# Power.net
KiCad netlist of a schematic drawn in Altium Designer
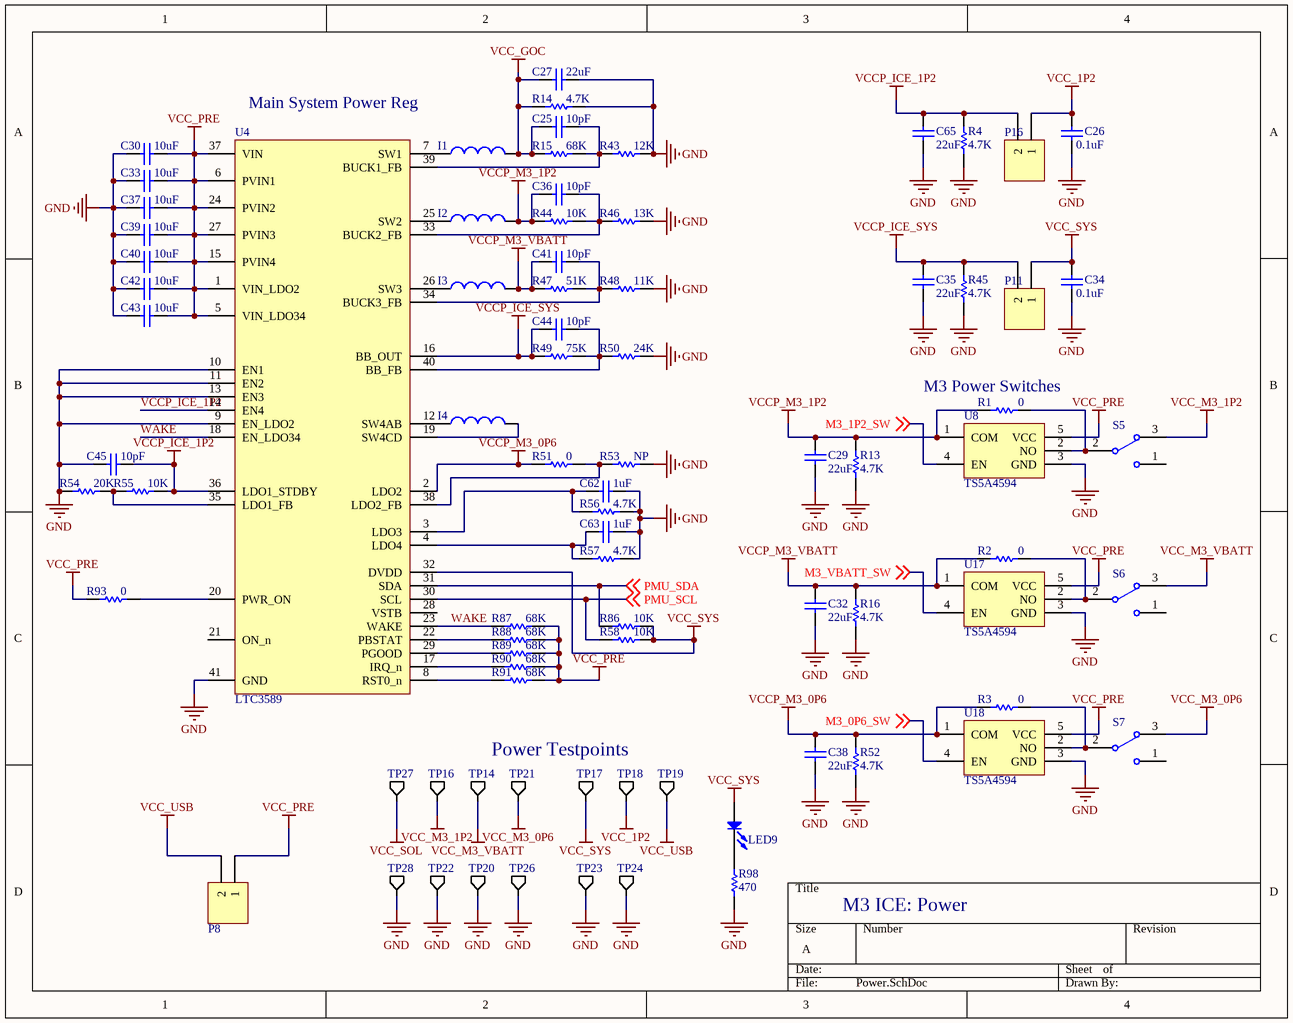
[diagram p0: Power.SchDoc]

(export (version "E")
  (design (tool "Eeschema 10.0.6"))
  (components
    (comp (ref "C25")
      (value "10pF")
      (footprint "0402")
      (description "Capacitor (Semiconductor SIM Model)")
      (fields
        (field (name "DISTPARTNO") "445-1235-1-ND")
        (field (name "MANPARTNO") "C1005C0G1H100D")
        (field (name "PUBLISHER") "Altium Limited")
      )
      (libsource (lib "Miscellaneous Devices") (part "Cap Semi"))
    )
    (comp (ref "C26")
      (value "0.1uF")
      (footprint "1608[0603]")
      (description "Capacitor (Semiconductor SIM Model)")
      (fields
        (field (name "DISTPARTNO") "1276-1005-1-ND")
        (field (name "MANPARTNO") "CL10B104KO8NNNC")
        (field (name "PUBLISHER") "Altium Limited")
      )
      (libsource (lib "Miscellaneous Devices") (part "Cap Semi"))
    )
    (comp (ref "C27")
      (value "22uF")
      (footprint "0805")
      (description "Capacitor (Semiconductor SIM Model)")
      (fields
        (field (name "DISTPARTNO") "587-2782-1-ND")
        (field (name "MANPARTNO") "LMK316AB7226ML-TR")
        (field (name "PUBLISHER") "Altium Limited")
      )
      (libsource (lib "M3") (part "Cap Chip"))
    )
    (comp (ref "C29")
      (value "22uF")
      (footprint "0805")
      (description "Capacitor (Semiconductor SIM Model)")
      (fields
        (field (name "DISTPARTNO") "587-2782-1-ND")
        (field (name "MANPARTNO") "LMK316AB7226ML-TR")
        (field (name "PUBLISHER") "Altium Limited")
      )
      (libsource (lib "M3") (part "Cap Chip"))
    )
    (comp (ref "C30")
      (value "10uF")
      (footprint "0805")
      (description "Capacitor (Semiconductor SIM Model)")
      (fields
        (field (name "DISTPARTNO") "445-6857-1-ND")
        (field (name "MANPARTNO") "C2012X7R1A106K")
        (field (name "PUBLISHER") "Altium Limited")
      )
      (libsource (lib "M3") (part "Cap Chip"))
    )
    (comp (ref "C32")
      (value "22uF")
      (footprint "0805")
      (description "Capacitor (Semiconductor SIM Model)")
      (fields
        (field (name "DISTPARTNO") "587-2782-1-ND")
        (field (name "MANPARTNO") "LMK316AB7226ML-TR")
        (field (name "PUBLISHER") "Altium Limited")
      )
      (libsource (lib "M3") (part "Cap Chip"))
    )
    (comp (ref "C33")
      (value "10uF")
      (footprint "0805")
      (description "Capacitor (Semiconductor SIM Model)")
      (fields
        (field (name "DISTPARTNO") "445-6857-1-ND")
        (field (name "MANPARTNO") "C2012X7R1A106K")
        (field (name "PUBLISHER") "Altium Limited")
      )
      (libsource (lib "M3") (part "Cap Chip"))
    )
    (comp (ref "C34")
      (value "0.1uF")
      (footprint "1608[0603]")
      (description "Capacitor (Semiconductor SIM Model)")
      (fields
        (field (name "DISTPARTNO") "1276-1005-1-ND")
        (field (name "MANPARTNO") "CL10B104KO8NNNC")
        (field (name "PUBLISHER") "Altium Limited")
      )
      (libsource (lib "Miscellaneous Devices") (part "Cap Semi"))
    )
    (comp (ref "C35")
      (value "22uF")
      (footprint "0805")
      (description "Capacitor (Semiconductor SIM Model)")
      (fields
        (field (name "DISTPARTNO") "587-2782-1-ND")
        (field (name "MANPARTNO") "LMK316AB7226ML-TR")
        (field (name "PUBLISHER") "Altium Limited")
      )
      (libsource (lib "M3") (part "Cap Chip"))
    )
    (comp (ref "C36")
      (value "10pF")
      (footprint "0402")
      (description "Capacitor (Semiconductor SIM Model)")
      (fields
        (field (name "DISTPARTNO") "445-1235-1-ND")
        (field (name "MANPARTNO") "C1005C0G1H100D")
        (field (name "PUBLISHER") "Altium Limited")
      )
      (libsource (lib "Miscellaneous Devices") (part "Cap Semi"))
    )
    (comp (ref "C37")
      (value "10uF")
      (footprint "0805")
      (description "Capacitor (Semiconductor SIM Model)")
      (fields
        (field (name "DISTPARTNO") "445-6857-1-ND")
        (field (name "MANPARTNO") "C2012X7R1A106K")
        (field (name "PUBLISHER") "Altium Limited")
      )
      (libsource (lib "M3") (part "Cap Chip"))
    )
    (comp (ref "C38")
      (value "22uF")
      (footprint "0805")
      (description "Capacitor (Semiconductor SIM Model)")
      (fields
        (field (name "DISTPARTNO") "587-2782-1-ND")
        (field (name "MANPARTNO") "LMK316AB7226ML-TR")
        (field (name "PUBLISHER") "Altium Limited")
      )
      (libsource (lib "M3") (part "Cap Chip"))
    )
    (comp (ref "C39")
      (value "10uF")
      (footprint "0805")
      (description "Capacitor (Semiconductor SIM Model)")
      (fields
        (field (name "DISTPARTNO") "445-6857-1-ND")
        (field (name "MANPARTNO") "C2012X7R1A106K")
        (field (name "PUBLISHER") "Altium Limited")
      )
      (libsource (lib "M3") (part "Cap Chip"))
    )
    (comp (ref "C40")
      (value "10uF")
      (footprint "0805")
      (description "Capacitor (Semiconductor SIM Model)")
      (fields
        (field (name "DISTPARTNO") "445-6857-1-ND")
        (field (name "MANPARTNO") "C2012X7R1A106K")
        (field (name "PUBLISHER") "Altium Limited")
      )
      (libsource (lib "M3") (part "Cap Chip"))
    )
    (comp (ref "C41")
      (value "10pF")
      (footprint "0402")
      (description "Capacitor (Semiconductor SIM Model)")
      (fields
        (field (name "DISTPARTNO") "445-1235-1-ND")
        (field (name "MANPARTNO") "C1005C0G1H100D")
        (field (name "PUBLISHER") "Altium Limited")
      )
      (libsource (lib "Miscellaneous Devices") (part "Cap Semi"))
    )
    (comp (ref "C42")
      (value "10uF")
      (footprint "0805")
      (description "Capacitor (Semiconductor SIM Model)")
      (fields
        (field (name "DISTPARTNO") "445-6857-1-ND")
        (field (name "MANPARTNO") "C2012X7R1A106K")
        (field (name "PUBLISHER") "Altium Limited")
      )
      (libsource (lib "M3") (part "Cap Chip"))
    )
    (comp (ref "C43")
      (value "10uF")
      (footprint "0805")
      (description "Capacitor (Semiconductor SIM Model)")
      (fields
        (field (name "DISTPARTNO") "445-6857-1-ND")
        (field (name "MANPARTNO") "C2012X7R1A106K")
        (field (name "PUBLISHER") "Altium Limited")
      )
      (libsource (lib "M3") (part "Cap Chip"))
    )
    (comp (ref "C44")
      (value "10pF")
      (footprint "0402")
      (description "Capacitor (Semiconductor SIM Model)")
      (fields
        (field (name "DISTPARTNO") "445-1235-1-ND")
        (field (name "MANPARTNO") "C1005C0G1H100D")
        (field (name "PUBLISHER") "Altium Limited")
      )
      (libsource (lib "Miscellaneous Devices") (part "Cap Semi"))
    )
    (comp (ref "C45")
      (value "10pF")
      (footprint "0402")
      (description "Capacitor (Semiconductor SIM Model)")
      (fields
        (field (name "DISTPARTNO") "445-1235-1-ND")
        (field (name "MANPARTNO") "C1005C0G1H100D")
        (field (name "PUBLISHER") "Altium Limited")
      )
      (libsource (lib "Miscellaneous Devices") (part "Cap Semi"))
    )
    (comp (ref "C62")
      (value "1uF")
      (footprint "0402")
      (description "Capacitor (Semiconductor SIM Model)")
      (fields
        (field (name "DISTPARTNO") "445-4991-1-ND")
        (field (name "MANPARTNO") "C1005X5R1A105M")
        (field (name "PUBLISHER") "Altium Limited")
      )
      (libsource (lib "Miscellaneous Devices") (part "Cap Semi"))
    )
    (comp (ref "C63")
      (value "1uF")
      (footprint "0402")
      (description "Capacitor (Semiconductor SIM Model)")
      (fields
        (field (name "DISTPARTNO") "445-4991-1-ND")
        (field (name "MANPARTNO") "C1005X5R1A105M")
        (field (name "PUBLISHER") "Altium Limited")
      )
      (libsource (lib "Miscellaneous Devices") (part "Cap Semi"))
    )
    (comp (ref "C65")
      (value "22uF")
      (footprint "0805")
      (description "Capacitor (Semiconductor SIM Model)")
      (fields
        (field (name "DISTPARTNO") "587-2782-1-ND")
        (field (name "MANPARTNO") "LMK316AB7226ML-TR")
        (field (name "PUBLISHER") "Altium Limited")
      )
      (libsource (lib "M3") (part "Cap Chip"))
    )
    (comp (ref "I1")
      (value "NR5040T1R5N")
      (footprint "INDUCTOR_.118x.142mm")
      (fields (field (name "DISTPARTNO") "541-1327-1-ND") (field (name "MANPARTNO") "IHLP1212AEER1R0M11"))
      (libsource (lib "M3") (part "IHLP1212"))
    )
    (comp (ref "I2")
      (value "NR5040T1R5N")
      (footprint "INDUCTOR_.118x.142mm")
      (fields (field (name "DISTPARTNO") "541-1327-1-ND") (field (name "MANPARTNO") "IHLP1212AEER1R0M11"))
      (libsource (lib "M3") (part "IHLP1212"))
    )
    (comp (ref "I3")
      (value "NR5040T1R5N")
      (footprint "INDUCTOR_.118x.142mm")
      (fields (field (name "DISTPARTNO") "541-1327-1-ND") (field (name "MANPARTNO") "IHLP1212AEER1R0M11"))
      (libsource (lib "M3") (part "IHLP1212"))
    )
    (comp (ref "I4")
      (value "NR5040T1R5N")
      (footprint "INDUCTOR_.118x.142mm")
      (fields (field (name "DISTPARTNO") "541-1327-1-ND") (field (name "MANPARTNO") "IHLP1212AEER1R0M11"))
      (libsource (lib "M3") (part "IHLP1212"))
    )
    (comp (ref "LED9")
      (value "LED 1206")
      (footprint "1206_LED")
      (fields (field (name "DISTPARTNO") "160-1169-1-ND") (field (name "MANPARTNO") "LTST-C150GKT"))
      (libsource (lib "M3") (part "LED 1206"))
    )
    (comp (ref "P8")
      (value "Header 2")
      (footprint "HDR1X2")
      (description "Header, 2-Pin")
      (fields (field (name "PUBLISHER") "Altium Limited"))
      (libsource (lib "Miscellaneous Connectors") (part "Header 2"))
    )
    (comp (ref "P11")
      (value "Header 2")
      (footprint "HDR1X2")
      (description "Header, 2-Pin")
      (fields (field (name "PUBLISHER") "Altium Limited"))
      (libsource (lib "Miscellaneous Connectors") (part "Header 2"))
    )
    (comp (ref "P16")
      (value "Header 2")
      (footprint "HDR1X2")
      (description "Header, 2-Pin")
      (fields (field (name "PUBLISHER") "Altium Limited"))
      (libsource (lib "Miscellaneous Connectors") (part "Header 2"))
    )
    (comp (ref "R1")
      (value "0")
      (footprint "0603")
      (description "Semiconductor Resistor")
      (fields
        (field (name "DISTPARTNO") "P0.0GCT-ND")
        (field (name "MANPARTNO") "ERJ-3GEY0R00V")
        (field (name "PUBLISHER") "Altium Limited")
      )
      (libsource (lib "M3") (part "Res Chip"))
    )
    (comp (ref "R2")
      (value "0")
      (footprint "0603")
      (description "Semiconductor Resistor")
      (fields
        (field (name "DISTPARTNO") "P0.0GCT-ND")
        (field (name "MANPARTNO") "ERJ-3GEY0R00V")
        (field (name "PUBLISHER") "Altium Limited")
      )
      (libsource (lib "M3") (part "Res Chip"))
    )
    (comp (ref "R3")
      (value "0")
      (footprint "0603")
      (description "Semiconductor Resistor")
      (fields
        (field (name "DISTPARTNO") "P0.0GCT-ND")
        (field (name "MANPARTNO") "ERJ-3GEY0R00V")
        (field (name "PUBLISHER") "Altium Limited")
      )
      (libsource (lib "M3") (part "Res Chip"))
    )
    (comp (ref "R4")
      (value "4.7K")
      (footprint "0603")
      (description "Semiconductor Resistor")
      (fields
        (field (name "DISTPARTNO") "P4.7KGCT-ND")
        (field (name "MANPARTNO") "ERJ-3GEYJ472V")
        (field (name "PUBLISHER") "Altium Limited")
      )
      (libsource (lib "M3") (part "Res Chip"))
    )
    (comp (ref "R13")
      (value "4.7K")
      (footprint "0603")
      (description "Semiconductor Resistor")
      (fields
        (field (name "DISTPARTNO") "P4.7KGCT-ND")
        (field (name "MANPARTNO") "ERJ-3GEYJ472V")
        (field (name "PUBLISHER") "Altium Limited")
      )
      (libsource (lib "M3") (part "Res Chip"))
    )
    (comp (ref "R14")
      (value "4.7K")
      (footprint "0603")
      (description "Semiconductor Resistor")
      (fields
        (field (name "DISTPARTNO") "P4.7KGCT-ND")
        (field (name "MANPARTNO") "ERJ-3GEYJ472V")
        (field (name "PUBLISHER") "Altium Limited")
      )
      (libsource (lib "M3") (part "Res Chip"))
    )
    (comp (ref "R15")
      (value "68K")
      (footprint "0402")
      (description "Semiconductor Resistor")
      (fields
        (field (name "DISTPARTNO") "P68.0KLCT-ND")
        (field (name "MANPARTNO") "ERJ-2RKF6802X")
        (field (name "PUBLISHER") "Altium Limited")
      )
      (libsource (lib "M3") (part "Res Chip"))
    )
    (comp (ref "R16")
      (value "4.7K")
      (footprint "0603")
      (description "Semiconductor Resistor")
      (fields
        (field (name "DISTPARTNO") "P4.7KGCT-ND")
        (field (name "MANPARTNO") "ERJ-3GEYJ472V")
        (field (name "PUBLISHER") "Altium Limited")
      )
      (libsource (lib "M3") (part "Res Chip"))
    )
    (comp (ref "R43")
      (value "12K")
      (footprint "0402")
      (description "Semiconductor Resistor")
      (fields
        (field (name "DISTPARTNO") "P12.0KLCT-ND")
        (field (name "MANPARTNO") "ERJ-2RKF1202X")
        (field (name "PUBLISHER") "Altium Limited")
      )
      (libsource (lib "M3") (part "Res Chip"))
    )
    (comp (ref "R44")
      (value "10K")
      (footprint "0402")
      (description "Semiconductor Resistor")
      (fields
        (field (name "DISTPARTNO") "P10.0KLCT-ND")
        (field (name "MANPARTNO") "ERJ-2RKF1002X")
        (field (name "PUBLISHER") "Altium Limited")
      )
      (libsource (lib "M3") (part "Res Chip"))
    )
    (comp (ref "R45")
      (value "4.7K")
      (footprint "0603")
      (description "Semiconductor Resistor")
      (fields
        (field (name "DISTPARTNO") "P4.7KGCT-ND")
        (field (name "MANPARTNO") "ERJ-3GEYJ472V")
        (field (name "PUBLISHER") "Altium Limited")
      )
      (libsource (lib "M3") (part "Res Chip"))
    )
    (comp (ref "R46")
      (value "13K")
      (footprint "0402")
      (description "Semiconductor Resistor")
      (fields
        (field (name "DISTPARTNO") "311-13.0KLRCT-ND")
        (field (name "MANPARTNO") "RC0402FR-0713KL")
        (field (name "PUBLISHER") "Altium Limited")
      )
      (libsource (lib "M3") (part "Res Chip"))
    )
    (comp (ref "R47")
      (value "51K")
      (footprint "0402")
      (description "Semiconductor Resistor")
      (fields
        (field (name "DISTPARTNO") "P51.0KLCT-ND")
        (field (name "MANPARTNO") "ERJ-2RKF5102X")
        (field (name "PUBLISHER") "Altium Limited")
      )
      (libsource (lib "M3") (part "Res Chip"))
    )
    (comp (ref "R48")
      (value "11K")
      (footprint "0402")
      (description "Semiconductor Resistor")
      (fields
        (field (name "DISTPARTNO") "P11.0KLCT-ND")
        (field (name "MANPARTNO") "ERJ-2RKF1102X")
        (field (name "PUBLISHER") "Altium Limited")
      )
      (libsource (lib "M3") (part "Res Chip"))
    )
    (comp (ref "R49")
      (value "75K")
      (footprint "0402")
      (description "Semiconductor Resistor")
      (fields
        (field (name "DISTPARTNO") "P75.0KLCT-ND")
        (field (name "MANPARTNO") "ERJ-2RKF7502X")
        (field (name "PUBLISHER") "Altium Limited")
      )
      (libsource (lib "M3") (part "Res Chip"))
    )
    (comp (ref "R50")
      (value "24K")
      (footprint "0402")
      (description "Semiconductor Resistor")
      (fields
        (field (name "DISTPARTNO") "RMCF0402FT24K0CT-ND")
        (field (name "MANPARTNO") "RMCF0402FT24K0")
        (field (name "PUBLISHER") "Altium Limited")
      )
      (libsource (lib "M3") (part "Res Chip"))
    )
    (comp (ref "R51")
      (value "0")
      (footprint "0402")
      (description "Semiconductor Resistor")
      (fields
        (field (name "DISTPARTNO") "P0.0JCT-ND")
        (field (name "MANPARTNO") "ERJ-2GE0R00X")
        (field (name "PUBLISHER") "Altium Limited")
      )
      (libsource (lib "M3") (part "Res Chip"))
    )
    (comp (ref "R52")
      (value "4.7K")
      (footprint "0603")
      (description "Semiconductor Resistor")
      (fields
        (field (name "DISTPARTNO") "P4.7KGCT-ND")
        (field (name "MANPARTNO") "ERJ-3GEYJ472V")
        (field (name "PUBLISHER") "Altium Limited")
      )
      (libsource (lib "M3") (part "Res Chip"))
    )
    (comp (ref "R53")
      (value "NP")
      (footprint "0402")
      (description "Semiconductor Resistor")
      (fields (field (name "Comment") "Res Chip") (field (name "PUBLISHER") "Altium Limited"))
      (libsource (lib "M3") (part "Res Chip"))
    )
    (comp (ref "R54")
      (value "20K")
      (footprint "0402")
      (description "Semiconductor Resistor")
      (fields
        (field (name "DISTPARTNO") "P20.0KLCT-ND")
        (field (name "MANPARTNO") "ERJ-2RKF2002X")
        (field (name "PUBLISHER") "Altium Limited")
      )
      (libsource (lib "M3") (part "Res Chip"))
    )
    (comp (ref "R55")
      (value "10K")
      (footprint "0402")
      (description "Semiconductor Resistor")
      (fields
        (field (name "DISTPARTNO") "P10.0KLCT-ND")
        (field (name "MANPARTNO") "ERJ-2RKF1002X")
        (field (name "PUBLISHER") "Altium Limited")
      )
      (libsource (lib "M3") (part "Res Chip"))
    )
    (comp (ref "R56")
      (value "4.7K")
      (footprint "0402")
      (description "Semiconductor Resistor")
      (fields
        (field (name "DISTPARTNO") "P4.70KLCT-ND")
        (field (name "MANPARTNO") "ERJ-2RKF4701X")
        (field (name "PUBLISHER") "Altium Limited")
      )
      (libsource (lib "M3") (part "Res Chip"))
    )
    (comp (ref "R57")
      (value "4.7K")
      (footprint "0402")
      (description "Semiconductor Resistor")
      (fields
        (field (name "DISTPARTNO") "P4.70KLCT-ND")
        (field (name "MANPARTNO") "ERJ-2RKF4701X")
        (field (name "PUBLISHER") "Altium Limited")
      )
      (libsource (lib "M3") (part "Res Chip"))
    )
    (comp (ref "R58")
      (value "10K")
      (footprint "0402")
      (description "Semiconductor Resistor")
      (fields
        (field (name "DISTPARTNO") "P10.0KLCT-ND")
        (field (name "MANPARTNO") "ERJ-2RKF1002X")
        (field (name "PUBLISHER") "Altium Limited")
      )
      (libsource (lib "M3") (part "Res Chip"))
    )
    (comp (ref "R86")
      (value "10K")
      (footprint "0402")
      (description "Semiconductor Resistor")
      (fields
        (field (name "DISTPARTNO") "P10.0KLCT-ND")
        (field (name "MANPARTNO") "ERJ-2RKF1002X")
        (field (name "PUBLISHER") "Altium Limited")
      )
      (libsource (lib "M3") (part "Res Chip"))
    )
    (comp (ref "R87")
      (value "68K")
      (footprint "0402")
      (description "Semiconductor Resistor")
      (fields
        (field (name "DISTPARTNO") "P68.0KLCT-ND")
        (field (name "MANPARTNO") "ERJ-2RKF6802X")
        (field (name "PUBLISHER") "Altium Limited")
      )
      (libsource (lib "M3") (part "Res Chip"))
    )
    (comp (ref "R88")
      (value "68K")
      (footprint "0402")
      (description "Semiconductor Resistor")
      (fields
        (field (name "DISTPARTNO") "P68.0KLCT-ND")
        (field (name "MANPARTNO") "ERJ-2RKF6802X")
        (field (name "PUBLISHER") "Altium Limited")
      )
      (libsource (lib "M3") (part "Res Chip"))
    )
    (comp (ref "R89")
      (value "68K")
      (footprint "0402")
      (description "Semiconductor Resistor")
      (fields
        (field (name "DISTPARTNO") "P68.0KLCT-ND")
        (field (name "MANPARTNO") "ERJ-2RKF6802X")
        (field (name "PUBLISHER") "Altium Limited")
      )
      (libsource (lib "M3") (part "Res Chip"))
    )
    (comp (ref "R90")
      (value "68K")
      (footprint "0402")
      (description "Semiconductor Resistor")
      (fields
        (field (name "DISTPARTNO") "P68.0KLCT-ND")
        (field (name "MANPARTNO") "ERJ-2RKF6802X")
        (field (name "PUBLISHER") "Altium Limited")
      )
      (libsource (lib "M3") (part "Res Chip"))
    )
    (comp (ref "R91")
      (value "68K")
      (footprint "0402")
      (description "Semiconductor Resistor")
      (fields
        (field (name "DISTPARTNO") "P68.0KLCT-ND")
        (field (name "MANPARTNO") "ERJ-2RKF6802X")
        (field (name "PUBLISHER") "Altium Limited")
      )
      (libsource (lib "M3") (part "Res Chip"))
    )
    (comp (ref "R93")
      (value "0")
      (footprint "0402")
      (description "Semiconductor Resistor")
      (fields
        (field (name "DISTPARTNO") "P0.0JCT-ND")
        (field (name "MANPARTNO") "ERJ-2GE0R00X")
        (field (name "PUBLISHER") "Altium Limited")
      )
      (libsource (lib "M3") (part "Res Chip"))
    )
    (comp (ref "R98")
      (value "470")
      (footprint "0603")
      (description "Semiconductor Resistor")
      (fields
        (field (name "DISTPARTNO") "P470GCT-ND")
        (field (name "MANPARTNO") "ERJ-3GEYJ471V")
        (field (name "PUBLISHER") "Altium Limited")
      )
      (libsource (lib "M3") (part "Res Chip"))
    )
    (comp (ref "S5")
      (value "OS102011MS2QN1")
      (footprint "SPDT_SW2")
      (description "SPDT Slide Switch")
      (fields (field (name "DISTPARTNO") "CKN9565-ND"))
      (libsource (lib "M3") (part "OS102011MS2QN1"))
    )
    (comp (ref "S6")
      (value "OS102011MS2QN1")
      (footprint "SPDT_SW2")
      (description "SPDT Slide Switch")
      (fields (field (name "DISTPARTNO") "CKN9565-ND"))
      (libsource (lib "M3") (part "OS102011MS2QN1"))
    )
    (comp (ref "S7")
      (value "OS102011MS2QN1")
      (footprint "SPDT_SW2")
      (description "SPDT Slide Switch")
      (fields (field (name "DISTPARTNO") "CKN9565-ND"))
      (libsource (lib "M3") (part "OS102011MS2QN1"))
    )
    (comp (ref "TP14") (value "TP") (footprint "TP") (libsource (lib "M3") (part "TP")))
    (comp (ref "TP16") (value "TP") (footprint "TP") (libsource (lib "M3") (part "TP")))
    (comp (ref "TP17") (value "TP") (footprint "TP") (libsource (lib "M3") (part "TP")))
    (comp (ref "TP18") (value "TP") (footprint "TP") (libsource (lib "M3") (part "TP")))
    (comp (ref "TP19") (value "TP") (footprint "TP") (libsource (lib "M3") (part "TP")))
    (comp (ref "TP20") (value "TP") (footprint "TP") (libsource (lib "M3") (part "TP")))
    (comp (ref "TP21") (value "TP") (footprint "TP") (libsource (lib "M3") (part "TP")))
    (comp (ref "TP22") (value "TP") (footprint "TP") (libsource (lib "M3") (part "TP")))
    (comp (ref "TP23") (value "TP") (footprint "TP") (libsource (lib "M3") (part "TP")))
    (comp (ref "TP24") (value "TP") (footprint "TP") (libsource (lib "M3") (part "TP")))
    (comp (ref "TP26") (value "TP") (footprint "TP") (libsource (lib "M3") (part "TP")))
    (comp (ref "TP27") (value "TP") (footprint "TP") (libsource (lib "M3") (part "TP")))
    (comp (ref "TP28") (value "TP") (footprint "TP") (libsource (lib "M3") (part "TP")))
    (comp (ref "U4")
      (value "LTC3589")
      (footprint "QFN-40")
      (fields (field (name "DISTPARTNO") "LTC3589EUJ-2#PBF-ND") (field (name "MANPARTNO") "LTC3589EUJ-2#PBF"))
      (libsource (lib "M3") (part "LTC3589"))
    )
    (comp (ref "U8")
      (value "TS5A4594")
      (footprint "SOT25")
      (description "SPST Analog Switch")
      (fields (field (name "DISTPARTNO") "296-17705-1-ND") (field (name "MANPARTNO") "TS5A4594DBVR"))
      (libsource (lib "M3") (part "TS5A4594"))
    )
    (comp (ref "U17")
      (value "TS5A4594")
      (footprint "SOT25")
      (description "SPST Analog Switch")
      (fields (field (name "DISTPARTNO") "296-17705-1-ND") (field (name "MANPARTNO") "TS5A4594DBVR"))
      (libsource (lib "M3") (part "TS5A4594"))
    )
    (comp (ref "U18")
      (value "TS5A4594")
      (footprint "SOT25")
      (description "SPST Analog Switch")
      (fields (field (name "DISTPARTNO") "296-17705-1-ND") (field (name "MANPARTNO") "TS5A4594DBVR"))
      (libsource (lib "M3") (part "TS5A4594"))
    )
  )
  (nets
    (net (code "1") (name "/WAKE") (class "Default")
      (node (ref "R87") (pin "1") (pinfunction "1_1") (pintype "passive"))
      (node (ref "U4") (pin "18") (pinfunction "EN_LDO34_18") (pintype "passive"))
      (node (ref "U4") (pin "23") (pinfunction "WAKE_23") (pintype "passive"))
    )
    (net (code "2") (name "GND") (class "Default")
      (node (ref "C26") (pin "1") (pinfunction "1_1") (pintype "passive"))
      (node (ref "C27") (pin "1") (pinfunction "1_1") (pintype "passive"))
      (node (ref "C29") (pin "1") (pinfunction "1_1") (pintype "passive"))
      (node (ref "C30") (pin "2") (pinfunction "2_2") (pintype "passive"))
      (node (ref "C32") (pin "1") (pinfunction "1_1") (pintype "passive"))
      (node (ref "C33") (pin "2") (pinfunction "2_2") (pintype "passive"))
      (node (ref "C34") (pin "1") (pinfunction "1_1") (pintype "passive"))
      (node (ref "C35") (pin "1") (pinfunction "1_1") (pintype "passive"))
      (node (ref "C37") (pin "2") (pinfunction "2_2") (pintype "passive"))
      (node (ref "C38") (pin "1") (pinfunction "1_1") (pintype "passive"))
      (node (ref "C39") (pin "2") (pinfunction "2_2") (pintype "passive"))
      (node (ref "C40") (pin "2") (pinfunction "2_2") (pintype "passive"))
      (node (ref "C42") (pin "2") (pinfunction "2_2") (pintype "passive"))
      (node (ref "C43") (pin "2") (pinfunction "2_2") (pintype "passive"))
      (node (ref "C45") (pin "2") (pinfunction "2_2") (pintype "passive"))
      (node (ref "C62") (pin "1") (pinfunction "1_1") (pintype "passive"))
      (node (ref "C63") (pin "1") (pinfunction "1_1") (pintype "passive"))
      (node (ref "C65") (pin "2") (pinfunction "2_2") (pintype "passive"))
      (node (ref "R13") (pin "1") (pinfunction "1_1") (pintype "passive"))
      (node (ref "R14") (pin "1") (pinfunction "1_1") (pintype "passive"))
      (node (ref "R16") (pin "1") (pinfunction "1_1") (pintype "passive"))
      (node (ref "R4") (pin "2") (pinfunction "2_2") (pintype "passive"))
      (node (ref "R43") (pin "2") (pinfunction "2_2") (pintype "passive"))
      (node (ref "R45") (pin "1") (pinfunction "1_1") (pintype "passive"))
      (node (ref "R46") (pin "2") (pinfunction "2_2") (pintype "passive"))
      (node (ref "R48") (pin "2") (pinfunction "2_2") (pintype "passive"))
      (node (ref "R50") (pin "2") (pinfunction "2_2") (pintype "passive"))
      (node (ref "R52") (pin "1") (pinfunction "1_1") (pintype "passive"))
      (node (ref "R53") (pin "2") (pinfunction "2_2") (pintype "passive"))
      (node (ref "R54") (pin "1") (pinfunction "1_1") (pintype "passive"))
      (node (ref "R56") (pin "2") (pinfunction "2_2") (pintype "passive"))
      (node (ref "R57") (pin "2") (pinfunction "2_2") (pintype "passive"))
      (node (ref "R98") (pin "1") (pinfunction "1_1") (pintype "passive"))
      (node (ref "TP20") (pin "1") (pinfunction "A_1") (pintype "passive"))
      (node (ref "TP22") (pin "1") (pinfunction "A_1") (pintype "passive"))
      (node (ref "TP23") (pin "1") (pinfunction "A_1") (pintype "passive"))
      (node (ref "TP24") (pin "1") (pinfunction "A_1") (pintype "passive"))
      (node (ref "TP26") (pin "1") (pinfunction "A_1") (pintype "passive"))
      (node (ref "TP28") (pin "1") (pinfunction "A_1") (pintype "passive"))
      (node (ref "U17") (pin "3") (pinfunction "GND_3") (pintype "passive"))
      (node (ref "U18") (pin "3") (pinfunction "GND_3") (pintype "passive"))
      (node (ref "U4") (pin "10") (pinfunction "EN1_10") (pintype "passive"))
      (node (ref "U4") (pin "11") (pinfunction "EN2_11") (pintype "passive"))
      (node (ref "U4") (pin "13") (pinfunction "EN3_13") (pintype "passive"))
      (node (ref "U4") (pin "41") (pinfunction "GND_41") (pintype "passive"))
      (node (ref "U4") (pin "9") (pinfunction "EN_LDO2_9") (pintype "passive"))
      (node (ref "U8") (pin "3") (pinfunction "GND_3") (pintype "passive"))
    )
    (net (code "3") (name "M3_0P6_SW") (class "Default")
      (node (ref "U18") (pin "4") (pinfunction "EN_4") (pintype "passive"))
    )
    (net (code "4") (name "M3_1P2_SW") (class "Default")
      (node (ref "U8") (pin "4") (pinfunction "EN_4") (pintype "passive"))
    )
    (net (code "5") (name "M3_VBATT_SW") (class "Default")
      (node (ref "U17") (pin "4") (pinfunction "EN_4") (pintype "passive"))
    )
    (net (code "6") (name "Net-(LED9-K)") (class "Default")
      (node (ref "LED9") (pin "2") (pinfunction "K_2") (pintype "passive"))
      (node (ref "R98") (pin "2") (pinfunction "2_2") (pintype "passive"))
    )
    (net (code "7") (name "Net-(U4-BB_FB)") (class "Default")
      (node (ref "C44") (pin "1") (pinfunction "1_1") (pintype "passive"))
      (node (ref "R49") (pin "2") (pinfunction "2_2") (pintype "passive"))
      (node (ref "R50") (pin "1") (pinfunction "1_1") (pintype "passive"))
      (node (ref "U4") (pin "40") (pinfunction "BB_FB_40") (pintype "passive"))
    )
    (net (code "8") (name "Net-(U4-BUCK1_FB)") (class "Default")
      (node (ref "C25") (pin "1") (pinfunction "1_1") (pintype "passive"))
      (node (ref "R15") (pin "2") (pinfunction "2_2") (pintype "passive"))
      (node (ref "R43") (pin "1") (pinfunction "1_1") (pintype "passive"))
      (node (ref "U4") (pin "39") (pinfunction "BUCK1_FB_39") (pintype "passive"))
    )
    (net (code "9") (name "Net-(U4-BUCK2_FB)") (class "Default")
      (node (ref "C36") (pin "1") (pinfunction "1_1") (pintype "passive"))
      (node (ref "R44") (pin "2") (pinfunction "2_2") (pintype "passive"))
      (node (ref "R46") (pin "1") (pinfunction "1_1") (pintype "passive"))
      (node (ref "U4") (pin "33") (pinfunction "BUCK2_FB_33") (pintype "passive"))
    )
    (net (code "10") (name "Net-(U4-BUCK3_FB)") (class "Default")
      (node (ref "C41") (pin "1") (pinfunction "1_1") (pintype "passive"))
      (node (ref "R47") (pin "2") (pinfunction "2_2") (pintype "passive"))
      (node (ref "R48") (pin "1") (pinfunction "1_1") (pintype "passive"))
      (node (ref "U4") (pin "34") (pinfunction "BUCK3_FB_34") (pintype "passive"))
    )
    (net (code "11") (name "Net-(U4-IRQ_n)") (class "Default")
      (node (ref "R90") (pin "1") (pinfunction "1_1") (pintype "passive"))
      (node (ref "U4") (pin "17") (pinfunction "IRQ_n_17") (pintype "passive"))
    )
    (net (code "12") (name "Net-(U4-LDO1_FB)") (class "Default")
      (node (ref "R54") (pin "2") (pinfunction "2_2") (pintype "passive"))
      (node (ref "R55") (pin "1") (pinfunction "1_1") (pintype "passive"))
      (node (ref "U4") (pin "35") (pinfunction "LDO1_FB_35") (pintype "passive"))
    )
    (net (code "13") (name "Net-(U4-LDO2_FB)") (class "Default")
      (node (ref "R51") (pin "2") (pinfunction "2_2") (pintype "passive"))
      (node (ref "R53") (pin "1") (pinfunction "1_1") (pintype "passive"))
      (node (ref "U4") (pin "38") (pinfunction "LDO2_FB_38") (pintype "passive"))
    )
    (net (code "14") (name "Net-(U4-LDO3)") (class "Default")
      (node (ref "C62") (pin "2") (pinfunction "2_2") (pintype "passive"))
      (node (ref "R56") (pin "1") (pinfunction "1_1") (pintype "passive"))
      (node (ref "U4") (pin "3") (pinfunction "LDO3_3") (pintype "passive"))
    )
    (net (code "15") (name "Net-(U4-LDO4)") (class "Default")
      (node (ref "C63") (pin "2") (pinfunction "2_2") (pintype "passive"))
      (node (ref "R57") (pin "1") (pinfunction "1_1") (pintype "passive"))
      (node (ref "U4") (pin "4") (pinfunction "LDO4_4") (pintype "passive"))
    )
    (net (code "16") (name "Net-(U4-PBSTAT)") (class "Default")
      (node (ref "R88") (pin "1") (pinfunction "1_1") (pintype "passive"))
      (node (ref "U4") (pin "22") (pinfunction "PBSTAT_22") (pintype "passive"))
    )
    (net (code "17") (name "Net-(U4-PGOOD)") (class "Default")
      (node (ref "R89") (pin "1") (pinfunction "1_1") (pintype "passive"))
      (node (ref "U4") (pin "29") (pinfunction "PGOOD_29") (pintype "passive"))
    )
    (net (code "18") (name "Net-(U4-PWR_ON)") (class "Default")
      (node (ref "R93") (pin "2") (pinfunction "2_2") (pintype "passive"))
      (node (ref "U4") (pin "20") (pinfunction "PWR_ON_20") (pintype "passive"))
    )
    (net (code "19") (name "Net-(U4-RST0_n)") (class "Default")
      (node (ref "R91") (pin "1") (pinfunction "1_1") (pintype "passive"))
      (node (ref "U4") (pin "8") (pinfunction "RST0_n_8") (pintype "passive"))
    )
    (net (code "20") (name "Net-(U4-SW1)") (class "Default")
      (node (ref "I1") (pin "1") (pinfunction "1_1") (pintype "passive"))
      (node (ref "U4") (pin "7") (pinfunction "SW1_7") (pintype "passive"))
    )
    (net (code "21") (name "Net-(U4-SW2)") (class "Default")
      (node (ref "I2") (pin "1") (pinfunction "1_1") (pintype "passive"))
      (node (ref "U4") (pin "25") (pinfunction "SW2_25") (pintype "passive"))
    )
    (net (code "22") (name "Net-(U4-SW3)") (class "Default")
      (node (ref "I3") (pin "1") (pinfunction "1_1") (pintype "passive"))
      (node (ref "U4") (pin "26") (pinfunction "SW3_26") (pintype "passive"))
    )
    (net (code "23") (name "Net-(U4-SW4AB)") (class "Default")
      (node (ref "I4") (pin "1") (pinfunction "1_1") (pintype "passive"))
      (node (ref "U4") (pin "12") (pinfunction "SW4AB_12") (pintype "passive"))
    )
    (net (code "24") (name "Net-(U4-SW4CD)") (class "Default")
      (node (ref "I4") (pin "2") (pinfunction "2_2") (pintype "passive"))
      (node (ref "U4") (pin "19") (pinfunction "SW4CD_19") (pintype "passive"))
    )
    (net (code "25") (name "Net-(U8-NO)") (class "Default")
      (node (ref "R1") (pin "1") (pinfunction "1_1") (pintype "passive"))
      (node (ref "S5") (pin "2") (pinfunction "2_2") (pintype "passive"))
      (node (ref "U8") (pin "2") (pinfunction "NO_2") (pintype "passive"))
    )
    (net (code "26") (name "Net-(U17-NO)") (class "Default")
      (node (ref "R2") (pin "1") (pinfunction "1_1") (pintype "passive"))
      (node (ref "S6") (pin "2") (pinfunction "2_2") (pintype "passive"))
      (node (ref "U17") (pin "2") (pinfunction "NO_2") (pintype "passive"))
    )
    (net (code "27") (name "Net-(U18-NO)") (class "Default")
      (node (ref "R3") (pin "1") (pinfunction "1_1") (pintype "passive"))
      (node (ref "S7") (pin "2") (pinfunction "2_2") (pintype "passive"))
      (node (ref "U18") (pin "2") (pinfunction "NO_2") (pintype "passive"))
    )
    (net (code "28") (name "PMU_SCL") (class "Default")
      (node (ref "R58") (pin "1") (pinfunction "1_1") (pintype "passive"))
      (node (ref "U4") (pin "30") (pinfunction "SCL_30") (pintype "passive"))
    )
    (net (code "29") (name "PMU_SDA") (class "Default")
      (node (ref "R86") (pin "1") (pinfunction "1_1") (pintype "passive"))
      (node (ref "U4") (pin "31") (pinfunction "SDA_31") (pintype "passive"))
    )
    (net (code "30") (name "VCCP_ICE_1P2") (class "Default")
      (node (ref "C45") (pin "1") (pinfunction "1_1") (pintype "passive"))
      (node (ref "C65") (pin "1") (pinfunction "1_1") (pintype "passive"))
      (node (ref "P16") (pin "2") (pinfunction "2_2") (pintype "passive"))
      (node (ref "R4") (pin "1") (pinfunction "1_1") (pintype "passive"))
      (node (ref "R55") (pin "2") (pinfunction "2_2") (pintype "passive"))
      (node (ref "U4") (pin "14") (pinfunction "EN4_14") (pintype "passive"))
      (node (ref "U4") (pin "36") (pinfunction "LDO1_STDBY_36") (pintype "passive"))
    )
    (net (code "31") (name "VCCP_ICE_SYS") (class "Default")
      (node (ref "C35") (pin "2") (pinfunction "2_2") (pintype "passive"))
      (node (ref "C44") (pin "2") (pinfunction "2_2") (pintype "passive"))
      (node (ref "P11") (pin "2") (pinfunction "2_2") (pintype "passive"))
      (node (ref "R45") (pin "2") (pinfunction "2_2") (pintype "passive"))
      (node (ref "R49") (pin "1") (pinfunction "1_1") (pintype "passive"))
      (node (ref "U4") (pin "16") (pinfunction "BB_OUT_16") (pintype "passive"))
    )
    (net (code "32") (name "VCCP_M3_0P6") (class "Default")
      (node (ref "C38") (pin "2") (pinfunction "2_2") (pintype "passive"))
      (node (ref "R3") (pin "2") (pinfunction "2_2") (pintype "passive"))
      (node (ref "R51") (pin "1") (pinfunction "1_1") (pintype "passive"))
      (node (ref "R52") (pin "2") (pinfunction "2_2") (pintype "passive"))
      (node (ref "U18") (pin "1") (pinfunction "COM_1") (pintype "passive"))
      (node (ref "U4") (pin "2") (pinfunction "LDO2_2") (pintype "passive"))
    )
    (net (code "33") (name "VCCP_M3_1P2") (class "Default")
      (node (ref "C29") (pin "2") (pinfunction "2_2") (pintype "passive"))
      (node (ref "C36") (pin "2") (pinfunction "2_2") (pintype "passive"))
      (node (ref "I2") (pin "2") (pinfunction "2_2") (pintype "passive"))
      (node (ref "R1") (pin "2") (pinfunction "2_2") (pintype "passive"))
      (node (ref "R13") (pin "2") (pinfunction "2_2") (pintype "passive"))
      (node (ref "R44") (pin "1") (pinfunction "1_1") (pintype "passive"))
      (node (ref "U8") (pin "1") (pinfunction "COM_1") (pintype "passive"))
    )
    (net (code "34") (name "VCCP_M3_VBATT") (class "Default")
      (node (ref "C32") (pin "2") (pinfunction "2_2") (pintype "passive"))
      (node (ref "C41") (pin "2") (pinfunction "2_2") (pintype "passive"))
      (node (ref "I3") (pin "2") (pinfunction "2_2") (pintype "passive"))
      (node (ref "R16") (pin "2") (pinfunction "2_2") (pintype "passive"))
      (node (ref "R2") (pin "2") (pinfunction "2_2") (pintype "passive"))
      (node (ref "R47") (pin "1") (pinfunction "1_1") (pintype "passive"))
      (node (ref "U17") (pin "1") (pinfunction "COM_1") (pintype "passive"))
    )
    (net (code "35") (name "VCC_1P2") (class "Default")
      (node (ref "C26") (pin "2") (pinfunction "2_2") (pintype "passive"))
      (node (ref "P16") (pin "1") (pinfunction "1_1") (pintype "passive"))
      (node (ref "TP18") (pin "1") (pinfunction "A_1") (pintype "passive"))
    )
    (net (code "36") (name "VCC_GOC") (class "Default")
      (node (ref "C25") (pin "2") (pinfunction "2_2") (pintype "passive"))
      (node (ref "C27") (pin "2") (pinfunction "2_2") (pintype "passive"))
      (node (ref "I1") (pin "2") (pinfunction "2_2") (pintype "passive"))
      (node (ref "R14") (pin "2") (pinfunction "2_2") (pintype "passive"))
      (node (ref "R15") (pin "1") (pinfunction "1_1") (pintype "passive"))
    )
    (net (code "37") (name "VCC_M3_0P6") (class "Default")
      (node (ref "S7") (pin "3") (pinfunction "3_3") (pintype "passive"))
      (node (ref "TP21") (pin "1") (pinfunction "A_1") (pintype "passive"))
    )
    (net (code "38") (name "VCC_M3_1P2") (class "Default")
      (node (ref "S5") (pin "3") (pinfunction "3_3") (pintype "passive"))
      (node (ref "TP16") (pin "1") (pinfunction "A_1") (pintype "passive"))
    )
    (net (code "39") (name "VCC_M3_VBATT") (class "Default")
      (node (ref "S6") (pin "3") (pinfunction "3_3") (pintype "passive"))
      (node (ref "TP14") (pin "1") (pinfunction "A_1") (pintype "passive"))
    )
    (net (code "40") (name "VCC_PRE") (class "Default")
      (node (ref "C30") (pin "1") (pinfunction "1_1") (pintype "passive"))
      (node (ref "C33") (pin "1") (pinfunction "1_1") (pintype "passive"))
      (node (ref "C37") (pin "1") (pinfunction "1_1") (pintype "passive"))
      (node (ref "C39") (pin "1") (pinfunction "1_1") (pintype "passive"))
      (node (ref "C40") (pin "1") (pinfunction "1_1") (pintype "passive"))
      (node (ref "C42") (pin "1") (pinfunction "1_1") (pintype "passive"))
      (node (ref "C43") (pin "1") (pinfunction "1_1") (pintype "passive"))
      (node (ref "P8") (pin "1") (pinfunction "1_1") (pintype "passive"))
      (node (ref "R87") (pin "2") (pinfunction "2_2") (pintype "passive"))
      (node (ref "R88") (pin "2") (pinfunction "2_2") (pintype "passive"))
      (node (ref "R89") (pin "2") (pinfunction "2_2") (pintype "passive"))
      (node (ref "R90") (pin "2") (pinfunction "2_2") (pintype "passive"))
      (node (ref "R91") (pin "2") (pinfunction "2_2") (pintype "passive"))
      (node (ref "R93") (pin "1") (pinfunction "1_1") (pintype "passive"))
      (node (ref "U17") (pin "5") (pinfunction "VCC_5") (pintype "passive"))
      (node (ref "U18") (pin "5") (pinfunction "VCC_5") (pintype "passive"))
      (node (ref "U4") (pin "1") (pinfunction "VIN_LDO2_1") (pintype "passive"))
      (node (ref "U4") (pin "15") (pinfunction "PVIN4_15") (pintype "passive"))
      (node (ref "U4") (pin "24") (pinfunction "PVIN2_24") (pintype "passive"))
      (node (ref "U4") (pin "27") (pinfunction "PVIN3_27") (pintype "passive"))
      (node (ref "U4") (pin "37") (pinfunction "VIN_37") (pintype "passive"))
      (node (ref "U4") (pin "5") (pinfunction "VIN_LDO34_5") (pintype "passive"))
      (node (ref "U4") (pin "6") (pinfunction "PVIN1_6") (pintype "passive"))
      (node (ref "U8") (pin "5") (pinfunction "VCC_5") (pintype "passive"))
    )
    (net (code "41") (name "VCC_SOL") (class "Default")
      (node (ref "TP27") (pin "1") (pinfunction "A_1") (pintype "passive"))
    )
    (net (code "42") (name "VCC_SYS") (class "Default")
      (node (ref "C34") (pin "2") (pinfunction "2_2") (pintype "passive"))
      (node (ref "LED9") (pin "1") (pinfunction "A_1") (pintype "passive"))
      (node (ref "P11") (pin "1") (pinfunction "1_1") (pintype "passive"))
      (node (ref "R58") (pin "2") (pinfunction "2_2") (pintype "passive"))
      (node (ref "R86") (pin "2") (pinfunction "2_2") (pintype "passive"))
      (node (ref "TP17") (pin "1") (pinfunction "A_1") (pintype "passive"))
      (node (ref "U4") (pin "32") (pinfunction "DVDD_32") (pintype "passive"))
    )
    (net (code "43") (name "VCC_USB") (class "Default")
      (node (ref "P8") (pin "2") (pinfunction "2_2") (pintype "passive"))
      (node (ref "TP19") (pin "1") (pinfunction "A_1") (pintype "passive"))
    )
    (net (code "44") (name "unconnected-(S5-Pad1)") (class "Default")
      (node (ref "S5") (pin "1") (pinfunction "1_1") (pintype "passive"))
    )
    (net (code "45") (name "unconnected-(S6-Pad1)") (class "Default")
      (node (ref "S6") (pin "1") (pinfunction "1_1") (pintype "passive"))
    )
    (net (code "46") (name "unconnected-(S7-Pad1)") (class "Default")
      (node (ref "S7") (pin "1") (pinfunction "1_1") (pintype "passive"))
    )
    (net (code "47") (name "unconnected-(U4-ON_n-Pad21)") (class "Default")
      (node (ref "U4") (pin "21") (pinfunction "ON_n_21") (pintype "passive"))
    )
    (net (code "48") (name "unconnected-(U4-VSTB-Pad28)") (class "Default")
      (node (ref "U4") (pin "28") (pinfunction "VSTB_28") (pintype "passive"))
    )
  )
)
